# Rectifire_PFC_Solar.net
KiCad netlist of a schematic drawn in Altium Designer
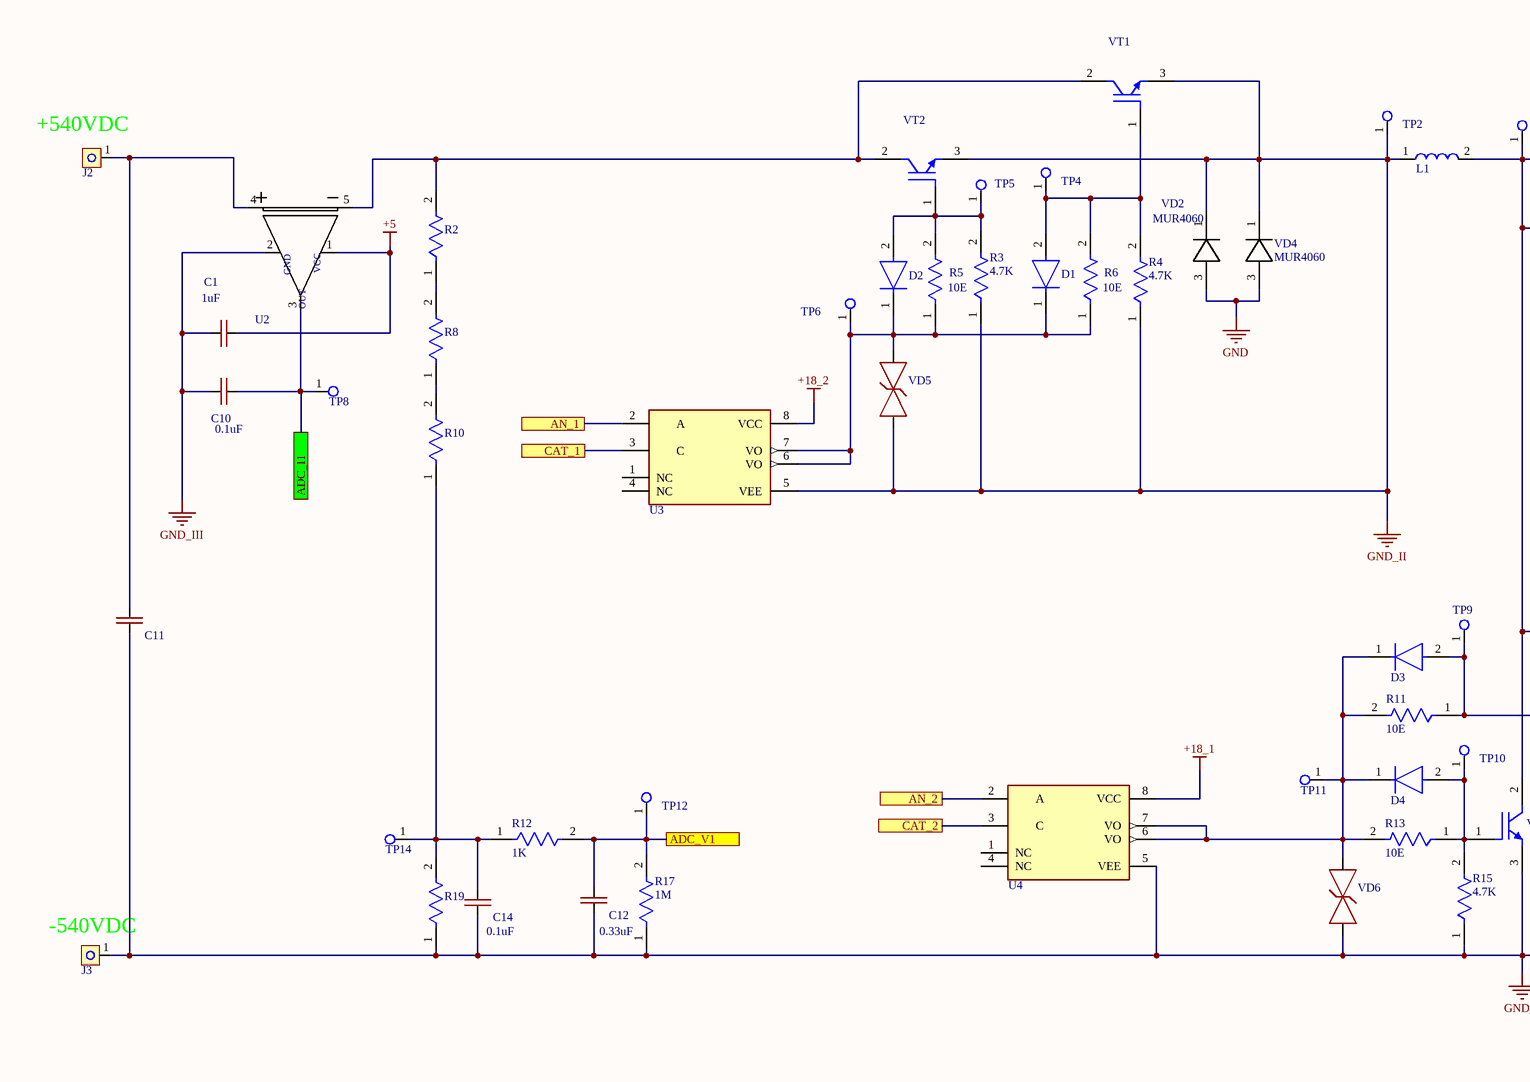
[diagram p0: Rectifire_PFC_Solar.SchDoc, top left]
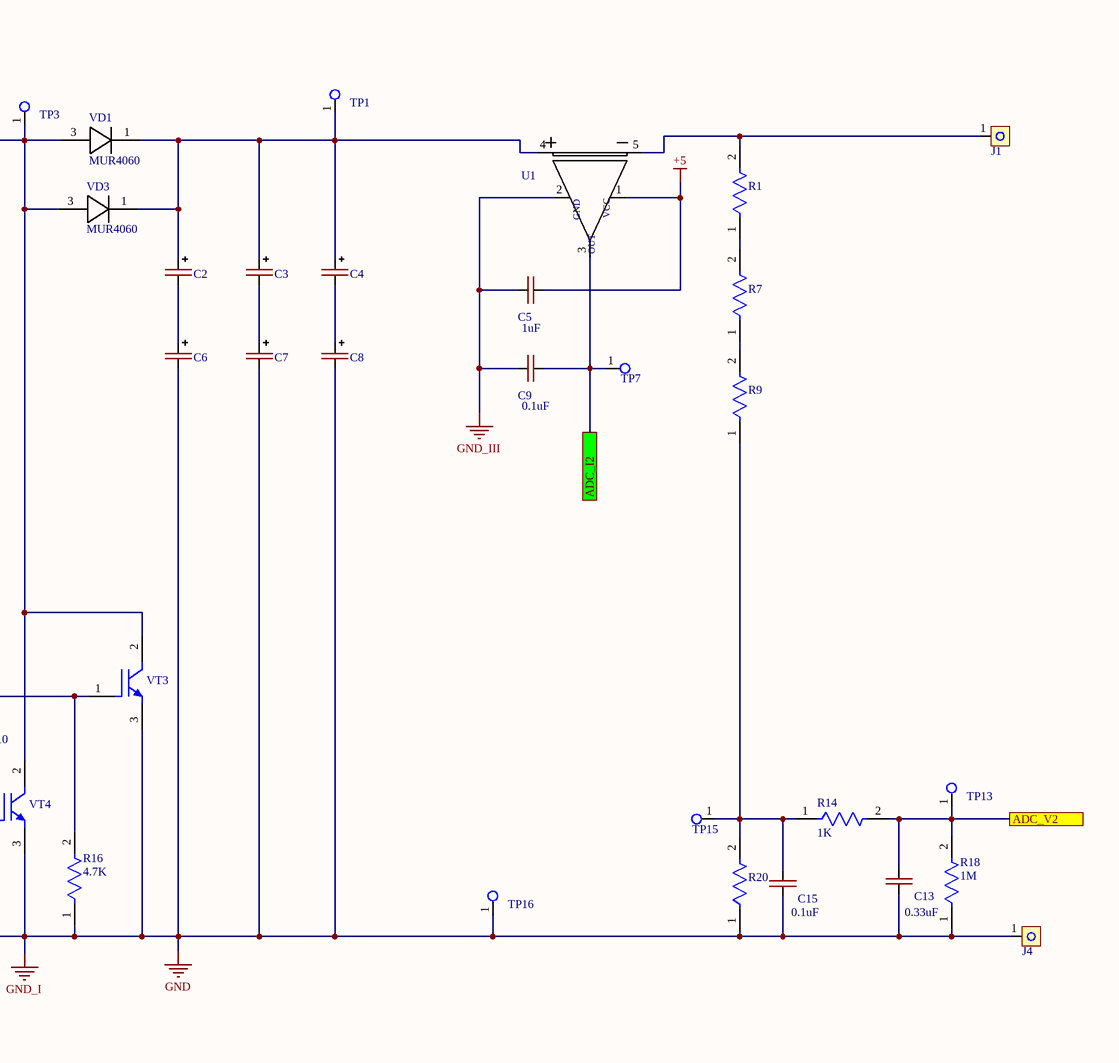
[diagram p1: Rectifire_PFC_Solar.SchDoc, top right]
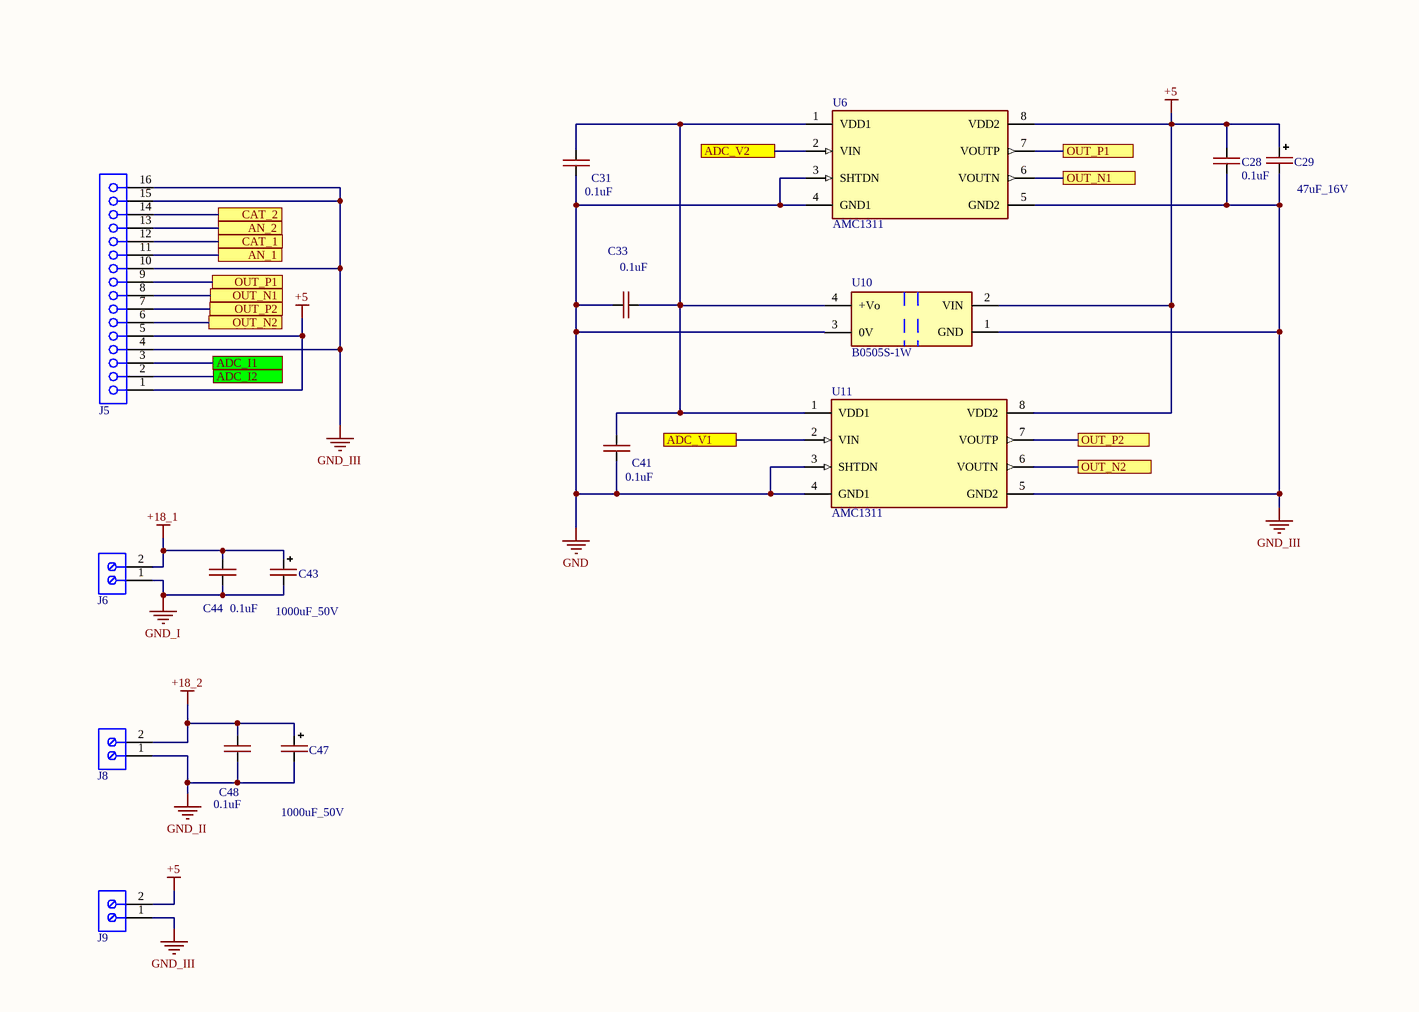
[diagram p2: Rectifire_PFC_Solar.SchDoc, bottom left]
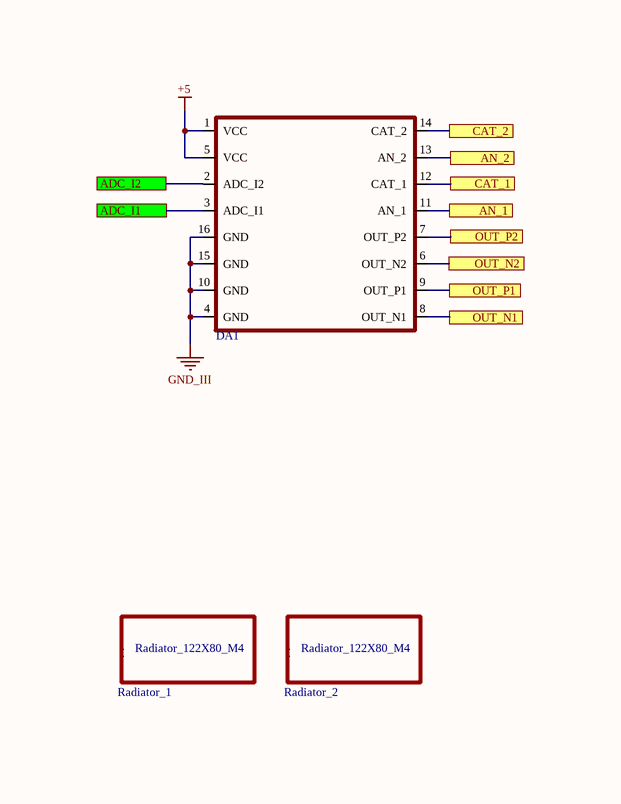
[diagram p3: Rectifire_PFC_Solar.SchDoc, bottom right]

(export (version "E")
  (design (tool "Eeschema 10.0.6"))
  (components
    (comp (ref "C1")
      (value "1uF")
      (footprint "CAP-0805")
      (libsource (lib "PASSIVE_COMPONENTS") (part "CAP-NON-POLAR"))
    )
    (comp (ref "C2")
      (value "CAP-POLAR")
      (footprint "CAP 100uF_500V 22x40mm")
      (libsource (lib "PASSIVE_COMPONENTS") (part "CAP-POLAR"))
    )
    (comp (ref "C3")
      (value "CAP-POLAR")
      (footprint "CAP 100uF_500V 22x40mm")
      (libsource (lib "PASSIVE_COMPONENTS") (part "CAP-POLAR"))
    )
    (comp (ref "C4")
      (value "CAP-POLAR")
      (footprint "CAP 100uF_500V 22x40mm")
      (libsource (lib "PASSIVE_COMPONENTS") (part "CAP-POLAR"))
    )
    (comp (ref "C5")
      (value "1uF")
      (footprint "CAP-0805")
      (libsource (lib "PASSIVE_COMPONENTS") (part "CAP-NON-POLAR"))
    )
    (comp (ref "C6")
      (value "CAP-POLAR")
      (footprint "CAP 100uF_500V 22x40mm")
      (libsource (lib "PASSIVE_COMPONENTS") (part "CAP-POLAR"))
    )
    (comp (ref "C7")
      (value "CAP-POLAR")
      (footprint "CAP 100uF_500V 22x40mm")
      (libsource (lib "PASSIVE_COMPONENTS") (part "CAP-POLAR"))
    )
    (comp (ref "C8")
      (value "CAP-POLAR")
      (footprint "CAP 100uF_500V 22x40mm")
      (libsource (lib "PASSIVE_COMPONENTS") (part "CAP-POLAR"))
    )
    (comp (ref "C9")
      (value "0.1uF")
      (footprint "CAP-0805")
      (libsource (lib "PASSIVE_COMPONENTS") (part "CAP-NON-POLAR"))
    )
    (comp (ref "C10")
      (value "0.1uF")
      (footprint "CAP-0805")
      (libsource (lib "PASSIVE_COMPONENTS") (part "CAP-NON-POLAR"))
    )
    (comp (ref "C11")
      (value "CAP-NON-POLAR")
      (footprint "CAP_4.7uF_630V")
      (libsource (lib "PASSIVE_COMPONENTS") (part "CAP-NON-POLAR"))
    )
    (comp (ref "C12")
      (value "0.33uF")
      (footprint "CAP-0805")
      (libsource (lib "PASSIVE_COMPONENTS") (part "CAP-NON-POLAR"))
    )
    (comp (ref "C13")
      (value "0.33uF")
      (footprint "CAP-0805")
      (libsource (lib "PASSIVE_COMPONENTS") (part "CAP-NON-POLAR"))
    )
    (comp (ref "C14")
      (value "0.1uF")
      (footprint "CAP-0805")
      (libsource (lib "PASSIVE_COMPONENTS") (part "CAP-NON-POLAR"))
    )
    (comp (ref "C15")
      (value "0.1uF")
      (footprint "CAP-0805")
      (libsource (lib "PASSIVE_COMPONENTS") (part "CAP-NON-POLAR"))
    )
    (comp (ref "C28")
      (value "0.1uF")
      (footprint "CAP-0805")
      (libsource (lib "PASSIVE_COMPONENTS") (part "CAP-NON-POLAR"))
    )
    (comp (ref "C29")
      (value "47uF_16V")
      (footprint "CAP-TAN-D")
      (libsource (lib "PASSIVE_COMPONENTS") (part "CAP-POLAR"))
    )
    (comp (ref "C31")
      (value "0.1uF")
      (footprint "CAP-0805")
      (libsource (lib "PASSIVE_COMPONENTS") (part "CAP-NON-POLAR"))
    )
    (comp (ref "C33")
      (value "0.1uF")
      (footprint "CAP-0805")
      (libsource (lib "PASSIVE_COMPONENTS") (part "CAP-NON-POLAR"))
    )
    (comp (ref "C41")
      (value "0.1uF")
      (footprint "CAP-0805")
      (libsource (lib "PASSIVE_COMPONENTS") (part "CAP-NON-POLAR"))
    )
    (comp (ref "C43")
      (value "1000uF_50V")
      (footprint "CAPPOL-16x25")
      (libsource (lib "PASSIVE_COMPONENTS") (part "CAP-POLAR"))
    )
    (comp (ref "C44")
      (value "0.1uF")
      (footprint "CAP-0805")
      (libsource (lib "PASSIVE_COMPONENTS") (part "CAP-NON-POLAR"))
    )
    (comp (ref "C47")
      (value "1000uF_50V")
      (footprint "CAPPOL-16x25")
      (libsource (lib "PASSIVE_COMPONENTS") (part "CAP-POLAR"))
    )
    (comp (ref "C48")
      (value "0.1uF")
      (footprint "CAP-0805")
      (libsource (lib "PASSIVE_COMPONENTS") (part "CAP-NON-POLAR"))
    )
    (comp (ref "D1") (value "US1G") (footprint "DO-214AA") (libsource (lib "Diodes") (part "US1G")))
    (comp (ref "D2") (value "US1G") (footprint "DO-214AA") (libsource (lib "Diodes") (part "US1G")))
    (comp (ref "D3") (value "US1G") (footprint "DO-214AA") (libsource (lib "Diodes") (part "US1G")))
    (comp (ref "D4") (value "US1G") (footprint "DO-214AA") (libsource (lib "Diodes") (part "US1G")))
    (comp (ref "DA1")
      (value "BOARD_PFC")
      (footprint "BOARD_PFC")
      (libsource (lib "BOARD_PFC") (part "BOARD_PFC"))
    )
    (comp (ref "J1")
      (value "MG_136_HT")
      (footprint "Conn_MEIGAN_MG136HT")
      (libsource (lib "") (part "Connector_MEIGAN_MG136HT_1"))
    )
    (comp (ref "J2")
      (value "MG_136_HT")
      (footprint "Conn_MEIGAN_MG136HT")
      (libsource (lib "Connectors") (part "Connector_MEIGAN_MG136HT"))
    )
    (comp (ref "J3")
      (value "MG_136_HT")
      (footprint "Conn_MEIGAN_MG136HT")
      (libsource (lib "Connectors") (part "Connector_MEIGAN_MG136HT"))
    )
    (comp (ref "J4")
      (value "MG_136_HT")
      (footprint "Conn_MEIGAN_MG136HT")
      (libsource (lib "") (part "Connector_MEIGAN_MG136HT_1"))
    )
    (comp (ref "J5")
      (value "61301611821")
      (footprint "61301611821")
      (description "WR-PHD Socket Header, THT, Vertical, pitch 2.54mm, 1 Row, 16P")
      (fields (field (name "MANUFACTURER") "Wurth Elektronik"))
      (libsource (lib "Altium_WR-PHD (rev22b)") (part "61301611821"))
    )
    (comp (ref "J6")
      (value "691102710002")
      (footprint "691102710002")
      (description "WR-TBL Series 102 Horizontal Entry Modular, THT, pitch 5mm, 2p")
      (fields (field (name "MANUFACTURER") "Wurth Elektronik"))
      (libsource (lib "Altium_WR-TBL (rev23f)") (part "691102710002"))
    )
    (comp (ref "J8")
      (value "691102710002")
      (footprint "691102710002")
      (description "WR-TBL Series 102 Horizontal Entry Modular, THT, pitch 5mm, 2p")
      (fields (field (name "MANUFACTURER") "Wurth Elektronik"))
      (libsource (lib "Altium_WR-TBL (rev23f)") (part "691102710002"))
    )
    (comp (ref "J9")
      (value "691102710002")
      (footprint "691102710002")
      (description "WR-TBL Series 102 Horizontal Entry Modular, THT, pitch 5mm, 2p")
      (fields (field (name "MANUFACTURER") "Wurth Elektronik"))
      (libsource (lib "Altium_WR-TBL (rev23f)") (part "691102710002"))
    )
    (comp (ref "L1") (value "Coil") (footprint "30A_10uH") (libsource (lib "Transformers") (part "Coil")))
    (comp (ref "R1")
      (value "RES_1210")
      (footprint "RES_SMD_1210_IPC_B")
      (libsource (lib "PASSIVE_COMPONENTS") (part "RES_1210"))
    )
    (comp (ref "R2")
      (value "RES_1210")
      (footprint "RES_SMD_1210_IPC_B")
      (libsource (lib "PASSIVE_COMPONENTS") (part "RES_1210"))
    )
    (comp (ref "R3")
      (value "4.7K")
      (footprint "RES-0805")
      (libsource (lib "PASSIVE_COMPONENTS") (part "RES-CONST"))
    )
    (comp (ref "R4")
      (value "4.7K")
      (footprint "RES-0805")
      (libsource (lib "PASSIVE_COMPONENTS") (part "RES-CONST"))
    )
    (comp (ref "R5")
      (value "10E")
      (footprint "RES_SMD_1210_IPC_A")
      (libsource (lib "PASSIVE_COMPONENTS") (part "RES_1210"))
    )
    (comp (ref "R6")
      (value "10E")
      (footprint "RES_SMD_1210_IPC_A")
      (libsource (lib "PASSIVE_COMPONENTS") (part "RES_1210"))
    )
    (comp (ref "R7")
      (value "RES_1210")
      (footprint "RES_SMD_1210_IPC_B")
      (libsource (lib "PASSIVE_COMPONENTS") (part "RES_1210"))
    )
    (comp (ref "R8")
      (value "RES_1210")
      (footprint "RES_SMD_1210_IPC_B")
      (libsource (lib "PASSIVE_COMPONENTS") (part "RES_1210"))
    )
    (comp (ref "R9")
      (value "RES_1210")
      (footprint "RES_SMD_1210_IPC_B")
      (libsource (lib "PASSIVE_COMPONENTS") (part "RES_1210"))
    )
    (comp (ref "R10")
      (value "RES_1210")
      (footprint "RES_SMD_1210_IPC_B")
      (libsource (lib "PASSIVE_COMPONENTS") (part "RES_1210"))
    )
    (comp (ref "R11")
      (value "10E")
      (footprint "RES_SMD_1210_IPC_A")
      (libsource (lib "PASSIVE_COMPONENTS") (part "RES_1210"))
    )
    (comp (ref "R12")
      (value "1K")
      (footprint "RES-0805")
      (libsource (lib "PASSIVE_COMPONENTS") (part "RES-CONST"))
    )
    (comp (ref "R13")
      (value "10E")
      (footprint "RES_SMD_1210_IPC_A")
      (libsource (lib "PASSIVE_COMPONENTS") (part "RES_1210"))
    )
    (comp (ref "R14")
      (value "1K")
      (footprint "RES-0805")
      (libsource (lib "PASSIVE_COMPONENTS") (part "RES-CONST"))
    )
    (comp (ref "R15")
      (value "4.7K")
      (footprint "RES-0805")
      (libsource (lib "PASSIVE_COMPONENTS") (part "RES-CONST"))
    )
    (comp (ref "R16")
      (value "4.7K")
      (footprint "RES-0805")
      (libsource (lib "PASSIVE_COMPONENTS") (part "RES-CONST"))
    )
    (comp (ref "R17")
      (value "1M")
      (footprint "RES-0805")
      (libsource (lib "PASSIVE_COMPONENTS") (part "RES-CONST"))
    )
    (comp (ref "R18")
      (value "1M")
      (footprint "RES-0805")
      (libsource (lib "PASSIVE_COMPONENTS") (part "RES-CONST"))
    )
    (comp (ref "R19")
      (value "RES_1210")
      (footprint "RES_SMD_1210_IPC_B")
      (libsource (lib "PASSIVE_COMPONENTS") (part "RES_1210"))
    )
    (comp (ref "R20")
      (value "RES_1210")
      (footprint "RES_SMD_1210_IPC_B")
      (libsource (lib "PASSIVE_COMPONENTS") (part "RES_1210"))
    )
    (comp (ref "Radiator_1")
      (value "Radiator_122X80_M4")
      (footprint "Radiator_122X80_M4")
      (libsource (lib "Radiator_122X80_M4") (part "Radiator_122X80_M4"))
    )
    (comp (ref "Radiator_2")
      (value "Radiator_122X80_M4")
      (footprint "Radiator_122X80_M4")
      (libsource (lib "Radiator_122X80_M4") (part "Radiator_122X80_M4"))
    )
    (comp (ref "TP1")
      (value "Test_Point_PCB")
      (footprint "Test_Point")
      (description "Test_Point")
      (libsource (lib "Connectors") (part "TP_PCB?"))
    )
    (comp (ref "TP2")
      (value "Test_Point_PCB")
      (footprint "Test_Point")
      (description "Test_Point")
      (libsource (lib "Connectors") (part "TP_PCB?"))
    )
    (comp (ref "TP3")
      (value "Test_Point_PCB")
      (footprint "Test_Point")
      (description "Test_Point")
      (libsource (lib "Connectors") (part "TP_PCB?"))
    )
    (comp (ref "TP4")
      (value "Test_Point_PCB")
      (footprint "Test_Point")
      (description "Test_Point")
      (libsource (lib "Connectors") (part "TP_PCB?"))
    )
    (comp (ref "TP5")
      (value "Test_Point_PCB")
      (footprint "Test_Point")
      (description "Test_Point")
      (libsource (lib "Connectors") (part "TP_PCB?"))
    )
    (comp (ref "TP6")
      (value "Test_Point_PCB")
      (footprint "Test_Point")
      (description "Test_Point")
      (libsource (lib "Connectors") (part "TP_PCB?"))
    )
    (comp (ref "TP7")
      (value "Test_Point_PCB")
      (footprint "Test_Point")
      (description "Test_Point")
      (libsource (lib "Connectors") (part "TP_PCB?"))
    )
    (comp (ref "TP8")
      (value "Test_Point_PCB")
      (footprint "Test_Point")
      (description "Test_Point")
      (libsource (lib "Connectors") (part "TP_PCB?"))
    )
    (comp (ref "TP9")
      (value "Test_Point_PCB")
      (footprint "Test_Point")
      (description "Test_Point")
      (libsource (lib "Connectors") (part "TP_PCB?"))
    )
    (comp (ref "TP10")
      (value "Test_Point_PCB")
      (footprint "Test_Point")
      (description "Test_Point")
      (libsource (lib "Connectors") (part "TP_PCB?"))
    )
    (comp (ref "TP11")
      (value "Test_Point_PCB")
      (footprint "Test_Point")
      (description "Test_Point")
      (libsource (lib "Connectors") (part "TP_PCB?"))
    )
    (comp (ref "TP12")
      (value "Test_Point_PCB")
      (footprint "Test_Point")
      (description "Test_Point")
      (libsource (lib "Connectors") (part "TP_PCB?"))
    )
    (comp (ref "TP13")
      (value "Test_Point_PCB")
      (footprint "Test_Point")
      (description "Test_Point")
      (libsource (lib "Connectors") (part "TP_PCB?"))
    )
    (comp (ref "TP14")
      (value "Test_Point_PCB")
      (footprint "Test_Point")
      (description "Test_Point")
      (libsource (lib "Connectors") (part "TP_PCB?"))
    )
    (comp (ref "TP15")
      (value "Test_Point_PCB")
      (footprint "Test_Point")
      (description "Test_Point")
      (libsource (lib "Connectors") (part "TP_PCB?"))
    )
    (comp (ref "TP16")
      (value "Test_Point_PCB")
      (footprint "Test_Point")
      (description "Test_Point")
      (libsource (lib "Connectors") (part "TP_PCB?"))
    )
    (comp (ref "U1")
      (value "ACS758")
      (footprint "ACS758-100")
      (libsource (lib "Integrated_Circuts") (part "ACS758"))
    )
    (comp (ref "U2")
      (value "ACS758")
      (footprint "ACS758-100")
      (libsource (lib "Integrated_Circuts") (part "ACS758"))
    )
    (comp (ref "U3")
      (value "HCPL-3120")
      (footprint "HCPL-3120")
      (libsource (lib "Integrated_Circuts") (part "HCPL-3120"))
    )
    (comp (ref "U4")
      (value "HCPL-3120")
      (footprint "HCPL-3120")
      (libsource (lib "Integrated_Circuts") (part "HCPL-3120"))
    )
    (comp (ref "U6")
      (value "AMC1311")
      (footprint "FP-DWV0008A-MFG")
      (libsource (lib "Integrated_Circuts") (part "AMC1311"))
    )
    (comp (ref "U10")
      (value "B0505S-1W")
      (footprint "B0505S-1W")
      (libsource (lib "Integrated_Circuts") (part "B0505S-1W"))
    )
    (comp (ref "U11")
      (value "AMC1311")
      (footprint "FP-DWV0008A-MFG")
      (libsource (lib "Integrated_Circuts") (part "AMC1311"))
    )
    (comp (ref "VD1") (value "MUR4060") (footprint "TO-247-2") (libsource (lib "Diodes") (part "MUR4060")))
    (comp (ref "VD2") (value "MUR4060") (footprint "TO-247-2") (libsource (lib "Diodes") (part "MUR4060")))
    (comp (ref "VD3") (value "MUR4060") (footprint "TO-247-2") (libsource (lib "Diodes") (part "MUR4060")))
    (comp (ref "VD4") (value "MUR4060") (footprint "TO-247-2") (libsource (lib "Diodes") (part "MUR4060")))
    (comp (ref "VD5")
      (value "Suppressor")
      (footprint "DO-214AA")
      (libsource (lib "Diodes") (part "Suppressor"))
    )
    (comp (ref "VD6")
      (value "Suppressor")
      (footprint "DO-214AA")
      (libsource (lib "Diodes") (part "Suppressor"))
    )
    (comp (ref "VT1")
      (value "IGBT 60N120T")
      (footprint "TO-264-3")
      (description "IGBT 60N120T TO-264-3")
      (libsource (lib "Transistors") (part "IGBT 60N120T"))
    )
    (comp (ref "VT2")
      (value "IGBT 60N120T")
      (footprint "TO-264-3")
      (description "IGBT 60N120T TO-264-3")
      (libsource (lib "Transistors") (part "IGBT 60N120T"))
    )
    (comp (ref "VT3")
      (value "IGBT 60N120T")
      (footprint "TO-264-3")
      (description "IGBT 60N120T TO-264-3")
      (libsource (lib "Transistors") (part "IGBT 60N120T"))
    )
    (comp (ref "VT4")
      (value "IGBT 60N120T")
      (footprint "TO-264-3")
      (description "IGBT 60N120T TO-264-3")
      (libsource (lib "Transistors") (part "IGBT 60N120T"))
    )
  )
  (nets
    (net (code "1") (name "+5") (class "Default")
      (node (ref "C1") (pin "2") (pinfunction "2_2") (pintype "passive"))
      (node (ref "C28") (pin "1") (pinfunction "1_1") (pintype "passive"))
      (node (ref "C29") (pin "1") (pinfunction "+_1") (pintype "passive"))
      (node (ref "C5") (pin "2") (pinfunction "2_2") (pintype "passive"))
      (node (ref "DA1") (pin "1") (pinfunction "VCC_1") (pintype "passive"))
      (node (ref "DA1") (pin "5") (pinfunction "VCC_5") (pintype "passive"))
      (node (ref "J5") (pin "1") (pinfunction "1_1") (pintype "passive"))
      (node (ref "J5") (pin "5") (pinfunction "5_5") (pintype "passive"))
      (node (ref "J9") (pin "2") (pinfunction "2_2") (pintype "passive"))
      (node (ref "U1") (pin "1") (pinfunction "+VCC_1") (pintype "passive"))
      (node (ref "U10") (pin "2") (pinfunction "VIN_2") (pintype "power_in"))
      (node (ref "U11") (pin "8") (pinfunction "VDD2_8") (pintype "power_in"))
      (node (ref "U2") (pin "1") (pinfunction "+VCC_1") (pintype "passive"))
      (node (ref "U6") (pin "8") (pinfunction "VDD2_8") (pintype "power_in"))
    )
    (net (code "2") (name "+18_1") (class "Default")
      (node (ref "C43") (pin "1") (pinfunction "+_1") (pintype "passive"))
      (node (ref "C44") (pin "2") (pinfunction "2_2") (pintype "passive"))
      (node (ref "J6") (pin "2") (pinfunction "2_2") (pintype "passive"))
      (node (ref "U4") (pin "8") (pinfunction "VCC_8") (pintype "power_in"))
    )
    (net (code "3") (name "+18_2") (class "Default")
      (node (ref "C47") (pin "1") (pinfunction "+_1") (pintype "passive"))
      (node (ref "C48") (pin "2") (pinfunction "2_2") (pintype "passive"))
      (node (ref "J8") (pin "2") (pinfunction "2_2") (pintype "passive"))
      (node (ref "U3") (pin "8") (pinfunction "VCC_8") (pintype "power_in"))
    )
    (net (code "4") (name "/ADC_I1") (class "Default")
      (node (ref "C10") (pin "2") (pinfunction "2_2") (pintype "passive"))
      (node (ref "DA1") (pin "3") (pinfunction "ADC_I1_3") (pintype "passive"))
      (node (ref "J5") (pin "3") (pinfunction "3_3") (pintype "passive"))
      (node (ref "TP8") (pin "1") (pinfunction "G9_1") (pintype "passive"))
      (node (ref "U2") (pin "3") (pinfunction "OUT_3") (pintype "passive"))
    )
    (net (code "5") (name "/ADC_I2") (class "Default")
      (node (ref "C9") (pin "2") (pinfunction "2_2") (pintype "passive"))
      (node (ref "DA1") (pin "2") (pinfunction "ADC_I2_2") (pintype "passive"))
      (node (ref "J5") (pin "2") (pinfunction "2_2") (pintype "passive"))
      (node (ref "TP7") (pin "1") (pinfunction "G9_1") (pintype "passive"))
      (node (ref "U1") (pin "3") (pinfunction "OUT_3") (pintype "passive"))
    )
    (net (code "6") (name "/ADC_V1") (class "Default")
      (node (ref "C12") (pin "2") (pinfunction "2_2") (pintype "passive"))
      (node (ref "R12") (pin "2") (pinfunction "2_2") (pintype "passive"))
      (node (ref "R17") (pin "2") (pinfunction "2_2") (pintype "passive"))
      (node (ref "TP12") (pin "1") (pinfunction "G9_1") (pintype "passive"))
      (node (ref "U11") (pin "2") (pinfunction "VIN_2") (pintype "input"))
    )
    (net (code "7") (name "/ADC_V2") (class "Default")
      (node (ref "C13") (pin "2") (pinfunction "2_2") (pintype "passive"))
      (node (ref "R14") (pin "2") (pinfunction "2_2") (pintype "passive"))
      (node (ref "R18") (pin "2") (pinfunction "2_2") (pintype "passive"))
      (node (ref "TP13") (pin "1") (pinfunction "G9_1") (pintype "passive"))
      (node (ref "U6") (pin "2") (pinfunction "VIN_2") (pintype "input"))
    )
    (net (code "8") (name "/AN_1") (class "Default")
      (node (ref "DA1") (pin "11") (pinfunction "AN_1_11") (pintype "passive"))
      (node (ref "J5") (pin "11") (pinfunction "11_11") (pintype "passive"))
      (node (ref "U3") (pin "2") (pinfunction "A_2") (pintype "passive"))
    )
    (net (code "9") (name "/AN_2") (class "Default")
      (node (ref "DA1") (pin "13") (pinfunction "AN_2_13") (pintype "passive"))
      (node (ref "J5") (pin "13") (pinfunction "13_13") (pintype "passive"))
      (node (ref "U4") (pin "2") (pinfunction "A_2") (pintype "passive"))
    )
    (net (code "10") (name "/CAT_1") (class "Default")
      (node (ref "DA1") (pin "12") (pinfunction "CAT_1_12") (pintype "passive"))
      (node (ref "J5") (pin "12") (pinfunction "12_12") (pintype "passive"))
      (node (ref "U3") (pin "3") (pinfunction "C_3") (pintype "passive"))
    )
    (net (code "11") (name "/CAT_2") (class "Default")
      (node (ref "DA1") (pin "14") (pinfunction "CAT_2_14") (pintype "passive"))
      (node (ref "J5") (pin "14") (pinfunction "14_14") (pintype "passive"))
      (node (ref "U4") (pin "3") (pinfunction "C_3") (pintype "passive"))
    )
    (net (code "12") (name "/OUT_N1") (class "Default")
      (node (ref "DA1") (pin "8") (pinfunction "OUT_N1_8") (pintype "passive"))
      (node (ref "J5") (pin "8") (pinfunction "8_8") (pintype "passive"))
      (node (ref "U6") (pin "6") (pinfunction "VOUTN_6") (pintype "output"))
    )
    (net (code "13") (name "/OUT_N2") (class "Default")
      (node (ref "DA1") (pin "6") (pinfunction "OUT_N2_6") (pintype "passive"))
      (node (ref "J5") (pin "6") (pinfunction "6_6") (pintype "passive"))
      (node (ref "U11") (pin "6") (pinfunction "VOUTN_6") (pintype "output"))
    )
    (net (code "14") (name "/OUT_P1") (class "Default")
      (node (ref "DA1") (pin "9") (pinfunction "OUT_P1_9") (pintype "passive"))
      (node (ref "J5") (pin "9") (pinfunction "9_9") (pintype "passive"))
      (node (ref "U6") (pin "7") (pinfunction "VOUTP_7") (pintype "output"))
    )
    (net (code "15") (name "/OUT_P2") (class "Default")
      (node (ref "DA1") (pin "7") (pinfunction "OUT_P2_7") (pintype "passive"))
      (node (ref "J5") (pin "7") (pinfunction "7_7") (pintype "passive"))
      (node (ref "U11") (pin "7") (pinfunction "VOUTP_7") (pintype "output"))
    )
    (net (code "16") (name "GND") (class "Default")
      (node (ref "C11") (pin "1") (pinfunction "1_1") (pintype "passive"))
      (node (ref "C12") (pin "1") (pinfunction "1_1") (pintype "passive"))
      (node (ref "C13") (pin "1") (pinfunction "1_1") (pintype "passive"))
      (node (ref "C14") (pin "1") (pinfunction "1_1") (pintype "passive"))
      (node (ref "C15") (pin "1") (pinfunction "1_1") (pintype "passive"))
      (node (ref "C31") (pin "1") (pinfunction "1_1") (pintype "passive"))
      (node (ref "C33") (pin "2") (pinfunction "2_2") (pintype "passive"))
      (node (ref "C41") (pin "1") (pinfunction "1_1") (pintype "passive"))
      (node (ref "C43") (pin "2") (pinfunction "-_2") (pintype "passive"))
      (node (ref "C44") (pin "1") (pinfunction "1_1") (pintype "passive"))
      (node (ref "C6") (pin "2") (pinfunction "-_2") (pintype "passive"))
      (node (ref "C7") (pin "2") (pinfunction "-_2") (pintype "passive"))
      (node (ref "C8") (pin "2") (pinfunction "-_2") (pintype "passive"))
      (node (ref "J3") (pin "1") (pinfunction "17_1") (pintype "passive"))
      (node (ref "J4") (pin "1") (pinfunction "17_1") (pintype "passive"))
      (node (ref "J6") (pin "1") (pinfunction "1_1") (pintype "passive"))
      (node (ref "R15") (pin "1") (pinfunction "1_1") (pintype "passive"))
      (node (ref "R16") (pin "1") (pinfunction "1_1") (pintype "passive"))
      (node (ref "R17") (pin "1") (pinfunction "1_1") (pintype "passive"))
      (node (ref "R18") (pin "1") (pinfunction "1_1") (pintype "passive"))
      (node (ref "R19") (pin "1") (pinfunction "1_1") (pintype "passive"))
      (node (ref "R20") (pin "1") (pinfunction "1_1") (pintype "passive"))
      (node (ref "TP16") (pin "1") (pinfunction "G9_1") (pintype "passive"))
      (node (ref "U10") (pin "3") (pinfunction "0V_3") (pintype "power_in"))
      (node (ref "U11") (pin "3") (pinfunction "SHTDN_3") (pintype "input"))
      (node (ref "U11") (pin "4") (pinfunction "GND1_4") (pintype "power_in"))
      (node (ref "U4") (pin "5") (pinfunction "VEE_5") (pintype "power_in"))
      (node (ref "U6") (pin "3") (pinfunction "SHTDN_3") (pintype "input"))
      (node (ref "U6") (pin "4") (pinfunction "GND1_4") (pintype "power_in"))
      (node (ref "VD2") (pin "3") (pinfunction "3_3") (pintype "passive"))
      (node (ref "VD4") (pin "3") (pinfunction "3_3") (pintype "passive"))
      (node (ref "VD6") (pin "1") (pinfunction "C_1") (pintype "passive"))
      (node (ref "VT3") (pin "3") (pinfunction "E_3") (pintype "passive"))
      (node (ref "VT4") (pin "3") (pinfunction "E_3") (pintype "passive"))
    )
    (net (code "17") (name "GND_II") (class "Default")
      (node (ref "C47") (pin "2") (pinfunction "-_2") (pintype "passive"))
      (node (ref "C48") (pin "1") (pinfunction "1_1") (pintype "passive"))
      (node (ref "J8") (pin "1") (pinfunction "1_1") (pintype "passive"))
      (node (ref "L1") (pin "1") (pinfunction "1_1") (pintype "passive"))
      (node (ref "R3") (pin "1") (pinfunction "1_1") (pintype "passive"))
      (node (ref "R4") (pin "1") (pinfunction "1_1") (pintype "passive"))
      (node (ref "TP2") (pin "1") (pinfunction "G9_1") (pintype "passive"))
      (node (ref "U3") (pin "5") (pinfunction "VEE_5") (pintype "power_in"))
      (node (ref "VD2") (pin "1") (pinfunction "1_1") (pintype "passive"))
      (node (ref "VD4") (pin "1") (pinfunction "1_1") (pintype "passive"))
      (node (ref "VD5") (pin "1") (pinfunction "C_1") (pintype "passive"))
      (node (ref "VT1") (pin "3") (pinfunction "E_3") (pintype "passive"))
      (node (ref "VT2") (pin "3") (pinfunction "E_3") (pintype "passive"))
    )
    (net (code "18") (name "GND_III") (class "Default")
      (node (ref "C1") (pin "1") (pinfunction "1_1") (pintype "passive"))
      (node (ref "C10") (pin "1") (pinfunction "1_1") (pintype "passive"))
      (node (ref "C28") (pin "2") (pinfunction "2_2") (pintype "passive"))
      (node (ref "C29") (pin "2") (pinfunction "-_2") (pintype "passive"))
      (node (ref "C5") (pin "1") (pinfunction "1_1") (pintype "passive"))
      (node (ref "C9") (pin "1") (pinfunction "1_1") (pintype "passive"))
      (node (ref "DA1") (pin "10") (pinfunction "GND_10") (pintype "passive"))
      (node (ref "DA1") (pin "15") (pinfunction "GND_15") (pintype "passive"))
      (node (ref "DA1") (pin "16") (pinfunction "GND_16") (pintype "passive"))
      (node (ref "DA1") (pin "4") (pinfunction "GND_4") (pintype "passive"))
      (node (ref "J5") (pin "10") (pinfunction "10_10") (pintype "passive"))
      (node (ref "J5") (pin "15") (pinfunction "15_15") (pintype "passive"))
      (node (ref "J5") (pin "16") (pinfunction "16_16") (pintype "passive"))
      (node (ref "J5") (pin "4") (pinfunction "4_4") (pintype "passive"))
      (node (ref "J9") (pin "1") (pinfunction "1_1") (pintype "passive"))
      (node (ref "U1") (pin "2") (pinfunction "GND_2") (pintype "passive"))
      (node (ref "U10") (pin "1") (pinfunction "GND_1") (pintype "power_in"))
      (node (ref "U11") (pin "5") (pinfunction "GND2_5") (pintype "power_in"))
      (node (ref "U2") (pin "2") (pinfunction "GND_2") (pintype "passive"))
      (node (ref "U6") (pin "5") (pinfunction "GND2_5") (pintype "power_in"))
    )
    (net (code "19") (name "Net-(C2-+)") (class "Default")
      (node (ref "C2") (pin "1") (pinfunction "+_1") (pintype "passive"))
      (node (ref "C3") (pin "1") (pinfunction "+_1") (pintype "passive"))
      (node (ref "C4") (pin "1") (pinfunction "+_1") (pintype "passive"))
      (node (ref "TP1") (pin "1") (pinfunction "G9_1") (pintype "passive"))
      (node (ref "U1") (pin "4") (pinfunction "+IP_4") (pintype "passive"))
      (node (ref "VD1") (pin "1") (pinfunction "1_1") (pintype "passive"))
      (node (ref "VD3") (pin "1") (pinfunction "1_1") (pintype "passive"))
    )
    (net (code "20") (name "Net-(C2--)") (class "Default")
      (node (ref "C2") (pin "2") (pinfunction "-_2") (pintype "passive"))
      (node (ref "C6") (pin "1") (pinfunction "+_1") (pintype "passive"))
    )
    (net (code "21") (name "Net-(C3--)") (class "Default")
      (node (ref "C3") (pin "2") (pinfunction "-_2") (pintype "passive"))
      (node (ref "C7") (pin "1") (pinfunction "+_1") (pintype "passive"))
    )
    (net (code "22") (name "Net-(C4--)") (class "Default")
      (node (ref "C4") (pin "2") (pinfunction "-_2") (pintype "passive"))
      (node (ref "C8") (pin "1") (pinfunction "+_1") (pintype "passive"))
    )
    (net (code "23") (name "Net-(D1-A)") (class "Default")
      (node (ref "D1") (pin "2") (pinfunction "A_2") (pintype "passive"))
      (node (ref "R4") (pin "2") (pinfunction "2_2") (pintype "passive"))
      (node (ref "R6") (pin "2") (pinfunction "2_2") (pintype "passive"))
      (node (ref "TP4") (pin "1") (pinfunction "G9_1") (pintype "passive"))
      (node (ref "VT1") (pin "1") (pinfunction "G_1") (pintype "passive"))
    )
    (net (code "24") (name "Net-(D1-C)") (class "Default")
      (node (ref "D1") (pin "1") (pinfunction "C_1") (pintype "passive"))
      (node (ref "D2") (pin "1") (pinfunction "C_1") (pintype "passive"))
      (node (ref "R5") (pin "1") (pinfunction "1_1") (pintype "passive"))
      (node (ref "R6") (pin "1") (pinfunction "1_1") (pintype "passive"))
      (node (ref "TP6") (pin "1") (pinfunction "G9_1") (pintype "passive"))
      (node (ref "U3") (pin "6") (pinfunction "VO_6") (pintype "output"))
      (node (ref "U3") (pin "7") (pinfunction "VO_7") (pintype "output"))
      (node (ref "VD5") (pin "2") (pinfunction "A_2") (pintype "passive"))
    )
    (net (code "25") (name "Net-(D2-A)") (class "Default")
      (node (ref "D2") (pin "2") (pinfunction "A_2") (pintype "passive"))
      (node (ref "R3") (pin "2") (pinfunction "2_2") (pintype "passive"))
      (node (ref "R5") (pin "2") (pinfunction "2_2") (pintype "passive"))
      (node (ref "TP5") (pin "1") (pinfunction "G9_1") (pintype "passive"))
      (node (ref "VT2") (pin "1") (pinfunction "G_1") (pintype "passive"))
    )
    (net (code "26") (name "Net-(D3-A)") (class "Default")
      (node (ref "D3") (pin "2") (pinfunction "A_2") (pintype "passive"))
      (node (ref "R11") (pin "1") (pinfunction "1_1") (pintype "passive"))
      (node (ref "R16") (pin "2") (pinfunction "2_2") (pintype "passive"))
      (node (ref "TP9") (pin "1") (pinfunction "G9_1") (pintype "passive"))
      (node (ref "VT3") (pin "1") (pinfunction "G_1") (pintype "passive"))
    )
    (net (code "27") (name "Net-(D3-C)") (class "Default")
      (node (ref "D3") (pin "1") (pinfunction "C_1") (pintype "passive"))
      (node (ref "D4") (pin "1") (pinfunction "C_1") (pintype "passive"))
      (node (ref "R11") (pin "2") (pinfunction "2_2") (pintype "passive"))
      (node (ref "R13") (pin "2") (pinfunction "2_2") (pintype "passive"))
      (node (ref "TP11") (pin "1") (pinfunction "G9_1") (pintype "passive"))
      (node (ref "U4") (pin "6") (pinfunction "VO_6") (pintype "output"))
      (node (ref "U4") (pin "7") (pinfunction "VO_7") (pintype "output"))
      (node (ref "VD6") (pin "2") (pinfunction "A_2") (pintype "passive"))
    )
    (net (code "28") (name "Net-(D4-A)") (class "Default")
      (node (ref "D4") (pin "2") (pinfunction "A_2") (pintype "passive"))
      (node (ref "R13") (pin "1") (pinfunction "1_1") (pintype "passive"))
      (node (ref "R15") (pin "2") (pinfunction "2_2") (pintype "passive"))
      (node (ref "TP10") (pin "1") (pinfunction "G9_1") (pintype "passive"))
      (node (ref "VT4") (pin "1") (pinfunction "G_1") (pintype "passive"))
    )
    (net (code "29") (name "Net-(J1-17)") (class "Default")
      (node (ref "J1") (pin "1") (pinfunction "17_1") (pintype "passive"))
      (node (ref "R1") (pin "2") (pinfunction "2_2") (pintype "passive"))
      (node (ref "U1") (pin "5") (pinfunction "-IP_5") (pintype "passive"))
    )
    (net (code "30") (name "Net-(J2-17)") (class "Default")
      (node (ref "C11") (pin "2") (pinfunction "2_2") (pintype "passive"))
      (node (ref "J2") (pin "1") (pinfunction "17_1") (pintype "passive"))
      (node (ref "U2") (pin "4") (pinfunction "+IP_4") (pintype "passive"))
    )
    (net (code "31") (name "Net-(R1-Pad1)") (class "Default")
      (node (ref "R1") (pin "1") (pinfunction "1_1") (pintype "passive"))
      (node (ref "R7") (pin "2") (pinfunction "2_2") (pintype "passive"))
    )
    (net (code "32") (name "Net-(R2-Pad1)") (class "Default")
      (node (ref "R2") (pin "1") (pinfunction "1_1") (pintype "passive"))
      (node (ref "R8") (pin "2") (pinfunction "2_2") (pintype "passive"))
    )
    (net (code "33") (name "Net-(R7-Pad1)") (class "Default")
      (node (ref "R7") (pin "1") (pinfunction "1_1") (pintype "passive"))
      (node (ref "R9") (pin "2") (pinfunction "2_2") (pintype "passive"))
    )
    (net (code "34") (name "Net-(R10-Pad2)") (class "Default")
      (node (ref "R10") (pin "2") (pinfunction "2_2") (pintype "passive"))
      (node (ref "R8") (pin "1") (pinfunction "1_1") (pintype "passive"))
    )
    (net (code "35") (name "Net-(TP3-G9)") (class "Default")
      (node (ref "L1") (pin "2") (pinfunction "2_2") (pintype "passive"))
      (node (ref "TP3") (pin "1") (pinfunction "G9_1") (pintype "passive"))
      (node (ref "VD1") (pin "3") (pinfunction "3_3") (pintype "passive"))
      (node (ref "VD3") (pin "3") (pinfunction "3_3") (pintype "passive"))
      (node (ref "VT3") (pin "2") (pinfunction "C_2") (pintype "passive"))
      (node (ref "VT4") (pin "2") (pinfunction "C_2") (pintype "passive"))
    )
    (net (code "36") (name "Net-(TP14-G9)") (class "Default")
      (node (ref "C14") (pin "2") (pinfunction "2_2") (pintype "passive"))
      (node (ref "R10") (pin "1") (pinfunction "1_1") (pintype "passive"))
      (node (ref "R12") (pin "1") (pinfunction "1_1") (pintype "passive"))
      (node (ref "R19") (pin "2") (pinfunction "2_2") (pintype "passive"))
      (node (ref "TP14") (pin "1") (pinfunction "G9_1") (pintype "passive"))
    )
    (net (code "37") (name "Net-(TP15-G9)") (class "Default")
      (node (ref "C15") (pin "2") (pinfunction "2_2") (pintype "passive"))
      (node (ref "R14") (pin "1") (pinfunction "1_1") (pintype "passive"))
      (node (ref "R20") (pin "2") (pinfunction "2_2") (pintype "passive"))
      (node (ref "R9") (pin "1") (pinfunction "1_1") (pintype "passive"))
      (node (ref "TP15") (pin "1") (pinfunction "G9_1") (pintype "passive"))
    )
    (net (code "38") (name "Net-(U2--IP)") (class "Default")
      (node (ref "R2") (pin "2") (pinfunction "2_2") (pintype "passive"))
      (node (ref "U2") (pin "5") (pinfunction "-IP_5") (pintype "passive"))
      (node (ref "VT1") (pin "2") (pinfunction "C_2") (pintype "passive"))
      (node (ref "VT2") (pin "2") (pinfunction "C_2") (pintype "passive"))
    )
    (net (code "39") (name "Net-(U10-+Vo)") (class "Default")
      (node (ref "C31") (pin "2") (pinfunction "2_2") (pintype "passive"))
      (node (ref "C33") (pin "1") (pinfunction "1_1") (pintype "passive"))
      (node (ref "C41") (pin "2") (pinfunction "2_2") (pintype "passive"))
      (node (ref "U10") (pin "4") (pinfunction "+Vo_4") (pintype "power_in"))
      (node (ref "U11") (pin "1") (pinfunction "VDD1_1") (pintype "power_in"))
      (node (ref "U6") (pin "1") (pinfunction "VDD1_1") (pintype "power_in"))
    )
    (net (code "40") (name "unconnected-(U3-NC-Pad1)") (class "Default")
      (node (ref "U3") (pin "1") (pinfunction "NC_1") (pintype "passive"))
    )
    (net (code "41") (name "unconnected-(U3-NC-Pad4)") (class "Default")
      (node (ref "U3") (pin "4") (pinfunction "NC_4") (pintype "passive"))
    )
    (net (code "42") (name "unconnected-(U4-NC-Pad1)") (class "Default")
      (node (ref "U4") (pin "1") (pinfunction "NC_1") (pintype "passive"))
    )
    (net (code "43") (name "unconnected-(U4-NC-Pad4)") (class "Default")
      (node (ref "U4") (pin "4") (pinfunction "NC_4") (pintype "passive"))
    )
  )
)
